# SparkFun_Qwiic_Presence_STHS34PF80.net
KiCad netlist of a schematic drawn in EAGLE
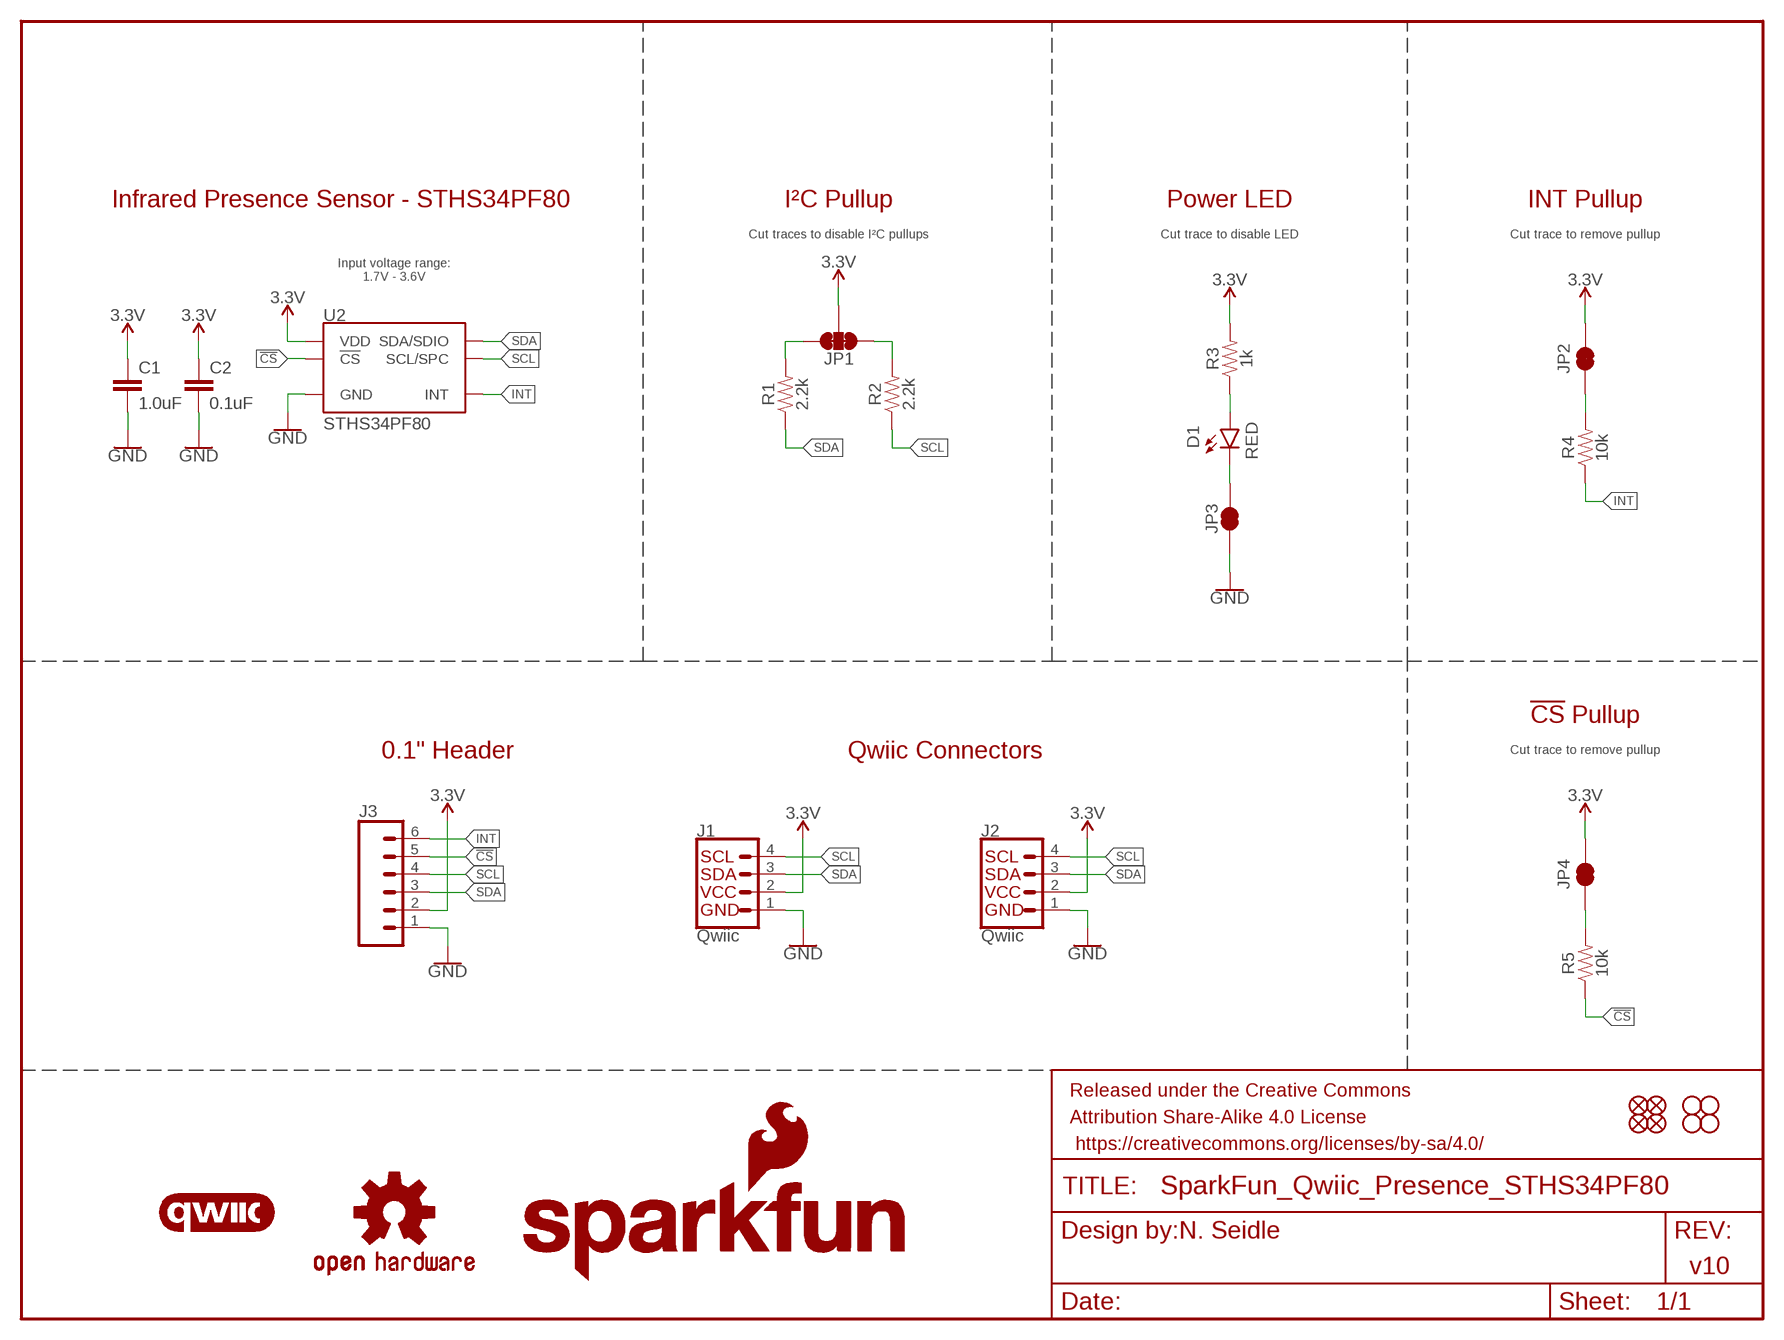
[diagram p0: schematic, sheet 1]

(export (version "E")
  (design (tool "Eeschema 10.0.6"))
  (components
    (comp (ref "C1")
      (value "1.0uF")
      (footprint "eagle-import:0603")
      (libsource (lib "eagle-import") (part "1.0UF-0603-16V-10%"))
    )
    (comp (ref "C2")
      (value "0.1uF")
      (footprint "eagle-import:0603")
      (libsource (lib "eagle-import") (part "0.1UF-0603-25V-(+80/-20%)"))
    )
    (comp (ref "D1")
      (value "RED")
      (footprint "eagle-import:LED-0603")
      (libsource (lib "eagle-import") (part "LED-RED0603"))
    )
    (comp (ref "FD1")
      (value "FIDUCIAL1X2")
      (footprint "eagle-import:FIDUCIAL-1X2")
      (libsource (lib "eagle-import") (part "FIDUCIAL1X2"))
    )
    (comp (ref "FD2")
      (value "FIDUCIAL1X2")
      (footprint "eagle-import:FIDUCIAL-1X2")
      (libsource (lib "eagle-import") (part "FIDUCIAL1X2"))
    )
    (comp (ref "FD3")
      (value "FIDUCIAL1X2")
      (footprint "eagle-import:FIDUCIAL-1X2")
      (libsource (lib "eagle-import") (part "FIDUCIAL1X2"))
    )
    (comp (ref "FD4")
      (value "FIDUCIAL1X2")
      (footprint "eagle-import:FIDUCIAL-1X2")
      (libsource (lib "eagle-import") (part "FIDUCIAL1X2"))
    )
    (comp (ref "FRAME2")
      (value "FRAME-LETTER")
      (footprint "eagle-import:CREATIVE_COMMONS")
      (libsource (lib "eagle-import") (part "FRAME-LETTER"))
    )
    (comp (ref "H1")
      (value "STAND-OFF")
      (footprint "eagle-import:STAND-OFF")
      (libsource (lib "eagle-import") (part "STAND-OFF"))
    )
    (comp (ref "H2")
      (value "STAND-OFF")
      (footprint "eagle-import:STAND-OFF")
      (libsource (lib "eagle-import") (part "STAND-OFF"))
    )
    (comp (ref "H3")
      (value "STAND-OFF")
      (footprint "eagle-import:STAND-OFF")
      (libsource (lib "eagle-import") (part "STAND-OFF"))
    )
    (comp (ref "H4")
      (value "STAND-OFF")
      (footprint "eagle-import:STAND-OFF")
      (libsource (lib "eagle-import") (part "STAND-OFF"))
    )
    (comp (ref "J1")
      (value "Qwiic")
      (footprint "eagle-import:JST04_1MM_RA")
      (libsource (lib "eagle-import") (part "QWIIC_CONNECTORJS-1MM"))
    )
    (comp (ref "J2")
      (value "Qwiic")
      (footprint "eagle-import:JST04_1MM_RA")
      (libsource (lib "eagle-import") (part "QWIIC_CONNECTORJS-1MM"))
    )
    (comp (ref "J3")
      (value "CONN_06NO_SILK_NO_POP")
      (footprint "eagle-import:1X06_NO_SILK")
      (libsource (lib "eagle-import") (part "CONN_06NO_SILK_NO_POP"))
    )
    (comp (ref "JP1")
      (value "JUMPER-SMT_3_2-NC_TRACE_SILK")
      (footprint "eagle-import:SMT-JUMPER_3_2-NC_TRACE_SILK")
      (libsource (lib "eagle-import") (part "JUMPER-SMT_3_2-NC_TRACE_SILK"))
    )
    (comp (ref "JP2")
      (value "JUMPER-SMT_2_NC_TRACE_SILK")
      (footprint "eagle-import:SMT-JUMPER_2_NC_TRACE_SILK")
      (libsource (lib "eagle-import") (part "JUMPER-SMT_2_NC_TRACE_SILK"))
    )
    (comp (ref "JP3")
      (value "JUMPER-SMT_2_NC_TRACE_SILK")
      (footprint "eagle-import:SMT-JUMPER_2_NC_TRACE_SILK")
      (libsource (lib "eagle-import") (part "JUMPER-SMT_2_NC_TRACE_SILK"))
    )
    (comp (ref "JP4")
      (value "JUMPER-SMT_2_NC_TRACE_SILK")
      (footprint "eagle-import:SMT-JUMPER_2_NC_TRACE_SILK")
      (libsource (lib "eagle-import") (part "JUMPER-SMT_2_NC_TRACE_SILK"))
    )
    (comp (ref "LOGO1")
      (value "OSHW-LOGOS")
      (footprint "eagle-import:OSHW-LOGO-S")
      (libsource (lib "eagle-import") (part "OSHW-LOGOS"))
    )
    (comp (ref "LOGO2")
      (value "SFE_LOGO_NAME_FLAME.1_INCH")
      (footprint "eagle-import:SFE_LOGO_NAME_FLAME_.1")
      (libsource (lib "eagle-import") (part "SFE_LOGO_NAME_FLAME.1_INCH"))
    )
    (comp (ref "LOGO3")
      (value "QWIIC_LOGO_CONNECTOR")
      (footprint "eagle-import:QWIIC_5.5MM")
      (libsource (lib "eagle-import") (part "QWIIC_LOGO_CONNECTOR"))
    )
    (comp (ref "LOGO4")
      (value "SFE_LOGO_NAME8_MM")
      (footprint "eagle-import:SFE_LOGO_NAME_8MM")
      (libsource (lib "eagle-import") (part "SFE_LOGO_NAME8_MM"))
    )
    (comp (ref "LOGO6")
      (value "SFE_LOGO_FLAME.1_INCH")
      (footprint "eagle-import:SFE_LOGO_FLAME_.1")
      (libsource (lib "eagle-import") (part "SFE_LOGO_FLAME.1_INCH"))
    )
    (comp (ref "R1")
      (value "2.2k")
      (footprint "eagle-import:0603")
      (libsource (lib "eagle-import") (part "2.2KOHM-0603-1/10W-1%"))
    )
    (comp (ref "R2")
      (value "2.2k")
      (footprint "eagle-import:0603")
      (libsource (lib "eagle-import") (part "2.2KOHM-0603-1/10W-1%"))
    )
    (comp (ref "R3")
      (value "1k")
      (footprint "eagle-import:0603")
      (libsource (lib "eagle-import") (part "1KOHM-0603-1/10W-1%"))
    )
    (comp (ref "R4")
      (value "10k")
      (footprint "eagle-import:0603")
      (libsource (lib "eagle-import") (part "10KOHM-0603-1/10W-1%"))
    )
    (comp (ref "R5")
      (value "10k")
      (footprint "eagle-import:0603")
      (libsource (lib "eagle-import") (part "10KOHM-0603-1/10W-1%"))
    )
    (comp (ref "U2")
      (value "STHS34PF80")
      (footprint "eagle-import:OLGA-10L")
      (libsource (lib "eagle-import") (part "STHS34PF80"))
    )
  )
  (nets
    (net (code "1") (name "/~{CS}") (class "Default")
      (node (ref "J3") (pin "5") (pinfunction "5_5") (pintype "passive"))
      (node (ref "R5") (pin "1") (pinfunction "1_1") (pintype "passive"))
      (node (ref "U2") (pin "3") (pinfunction "~{CS}_3") (pintype "input"))
    )
    (net (code "2") (name "3.3V") (class "Default")
      (node (ref "C1") (pin "1") (pinfunction "1_1") (pintype "passive"))
      (node (ref "C2") (pin "1") (pinfunction "1_1") (pintype "passive"))
      (node (ref "J1") (pin "2") (pinfunction "2_2") (pintype "power_in"))
      (node (ref "J2") (pin "2") (pinfunction "2_2") (pintype "power_in"))
      (node (ref "J3") (pin "2") (pinfunction "2_2") (pintype "passive"))
      (node (ref "JP1") (pin "2") (pinfunction "2_2") (pintype "passive"))
      (node (ref "JP2") (pin "2") (pinfunction "2_2") (pintype "passive"))
      (node (ref "JP4") (pin "2") (pinfunction "2_2") (pintype "passive"))
      (node (ref "R3") (pin "2") (pinfunction "2_2") (pintype "passive"))
      (node (ref "U2") (pin "6") (pinfunction "VDD_6") (pintype "power_in"))
      (node (ref "U2") (pin "9") (pinfunction "VDD_9") (pintype "power_in"))
    )
    (net (code "3") (name "GND") (class "Default")
      (node (ref "C1") (pin "2") (pinfunction "2_2") (pintype "passive"))
      (node (ref "C2") (pin "2") (pinfunction "2_2") (pintype "passive"))
      (node (ref "J1") (pin "1") (pinfunction "1_1") (pintype "power_in"))
      (node (ref "J2") (pin "1") (pinfunction "1_1") (pintype "power_in"))
      (node (ref "J3") (pin "1") (pinfunction "1_1") (pintype "passive"))
      (node (ref "JP3") (pin "1") (pinfunction "1_1") (pintype "passive"))
      (node (ref "U2") (pin "2") (pinfunction "GND_2") (pintype "power_in"))
      (node (ref "U2") (pin "7") (pinfunction "GND_7") (pintype "power_in"))
      (node (ref "U2") (pin "8") (pinfunction "GND_8") (pintype "power_in"))
    )
    (net (code "4") (name "INT") (class "Default")
      (node (ref "J3") (pin "6") (pinfunction "6_6") (pintype "passive"))
      (node (ref "R4") (pin "1") (pinfunction "1_1") (pintype "passive"))
      (node (ref "U2") (pin "10") (pinfunction "INT_10") (pintype "output"))
    )
    (net (code "5") (name "Net-(D1-PadA)") (class "Default")
      (node (ref "D1") (pin "A") (pinfunction "A_A") (pintype "passive"))
      (node (ref "R3") (pin "1") (pinfunction "1_1") (pintype "passive"))
    )
    (net (code "6") (name "Net-(D1-PadC)") (class "Default")
      (node (ref "D1") (pin "C") (pinfunction "C_C") (pintype "passive"))
      (node (ref "JP3") (pin "2") (pinfunction "2_2") (pintype "passive"))
    )
    (net (code "7") (name "Net-(JP1-Pad1)") (class "Default")
      (node (ref "JP1") (pin "1") (pinfunction "1_1") (pintype "passive"))
      (node (ref "R2") (pin "2") (pinfunction "2_2") (pintype "passive"))
    )
    (net (code "8") (name "Net-(JP1-Pad3)") (class "Default")
      (node (ref "JP1") (pin "3") (pinfunction "3_3") (pintype "passive"))
      (node (ref "R1") (pin "2") (pinfunction "2_2") (pintype "passive"))
    )
    (net (code "9") (name "Net-(JP2-Pad1)") (class "Default")
      (node (ref "JP2") (pin "1") (pinfunction "1_1") (pintype "passive"))
      (node (ref "R4") (pin "2") (pinfunction "2_2") (pintype "passive"))
    )
    (net (code "10") (name "Net-(JP4-Pad1)") (class "Default")
      (node (ref "JP4") (pin "1") (pinfunction "1_1") (pintype "passive"))
      (node (ref "R5") (pin "2") (pinfunction "2_2") (pintype "passive"))
    )
    (net (code "11") (name "SCL") (class "Default")
      (node (ref "J1") (pin "4") (pinfunction "4_4") (pintype "passive"))
      (node (ref "J2") (pin "4") (pinfunction "4_4") (pintype "passive"))
      (node (ref "J3") (pin "4") (pinfunction "4_4") (pintype "passive"))
      (node (ref "R2") (pin "1") (pinfunction "1_1") (pintype "passive"))
      (node (ref "U2") (pin "1") (pinfunction "SCL/SPC_1") (pintype "bidirectional"))
    )
    (net (code "12") (name "SDA") (class "Default")
      (node (ref "J1") (pin "3") (pinfunction "3_3") (pintype "passive"))
      (node (ref "J2") (pin "3") (pinfunction "3_3") (pintype "passive"))
      (node (ref "J3") (pin "3") (pinfunction "3_3") (pintype "passive"))
      (node (ref "R1") (pin "1") (pinfunction "1_1") (pintype "passive"))
      (node (ref "U2") (pin "4") (pinfunction "SDA/SDIO_4") (pintype "bidirectional"))
    )
  )
)
